# rx20.net
KiCad netlist of a schematic drawn in EAGLE
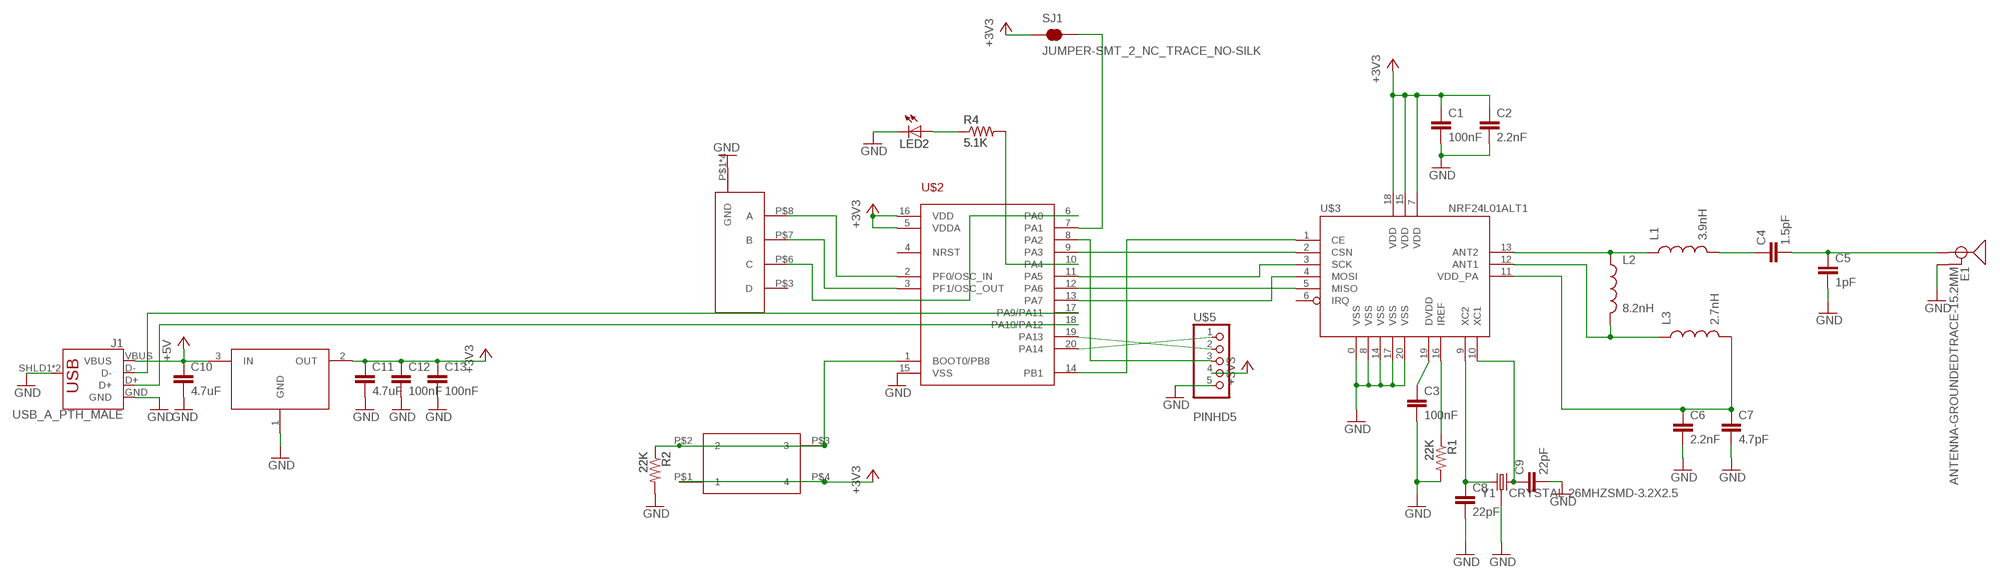
[diagram p0: schematic, sheet 1]

(export (version "E")
  (design (tool "Eeschema 10.0.6"))
  (components
    (comp (ref "C1")
      (value "100nF")
      (footprint "eagle-import:0805")
      (libsource (lib "eagle-import") (part "CAP0805"))
    )
    (comp (ref "C2")
      (value "2.2nF")
      (footprint "eagle-import:0805")
      (libsource (lib "eagle-import") (part "CAP0805"))
    )
    (comp (ref "C3")
      (value "100nF")
      (footprint "eagle-import:0805")
      (libsource (lib "eagle-import") (part "CAP0805"))
    )
    (comp (ref "C4")
      (value "1.5pF")
      (footprint "eagle-import:0805")
      (libsource (lib "eagle-import") (part "CAP0805"))
    )
    (comp (ref "C5")
      (value "1pF")
      (footprint "eagle-import:0805")
      (libsource (lib "eagle-import") (part "CAP0805"))
    )
    (comp (ref "C6")
      (value "2.2nF")
      (footprint "eagle-import:0805")
      (libsource (lib "eagle-import") (part "CAP0805"))
    )
    (comp (ref "C7")
      (value "4.7pF")
      (footprint "eagle-import:0805")
      (libsource (lib "eagle-import") (part "CAP0805"))
    )
    (comp (ref "C8")
      (value "22pF")
      (footprint "eagle-import:0805")
      (libsource (lib "eagle-import") (part "CAP0805"))
    )
    (comp (ref "C9")
      (value "22pF")
      (footprint "eagle-import:0805")
      (libsource (lib "eagle-import") (part "CAP0805"))
    )
    (comp (ref "C10")
      (value "4.7uF")
      (footprint "eagle-import:0805")
      (libsource (lib "eagle-import") (part "CAP0805"))
    )
    (comp (ref "C11")
      (value "4.7uF")
      (footprint "eagle-import:0805")
      (libsource (lib "eagle-import") (part "CAP0805"))
    )
    (comp (ref "C12")
      (value "100nF")
      (footprint "eagle-import:0805")
      (libsource (lib "eagle-import") (part "CAP0805"))
    )
    (comp (ref "C13")
      (value "100nF")
      (footprint "eagle-import:0805")
      (libsource (lib "eagle-import") (part "CAP0805"))
    )
    (comp (ref "E1")
      (value "ANTENNA-GROUNDEDTRACE-15.2MM")
      (footprint "eagle-import:TRACE_ANTENNA_2.4GHZ_15.2MM")
      (libsource (lib "eagle-import") (part "ANTENNA-GROUNDEDTRACE-15.2MM"))
    )
    (comp (ref "J1")
      (value "USB_A_PTH_MALE")
      (footprint "eagle-import:USB-A-H")
      (libsource (lib "eagle-import") (part "USB_A_PTH_MALE"))
    )
    (comp (ref "L1")
      (value "3.9nH")
      (footprint "eagle-import:0805")
      (libsource (lib "eagle-import") (part "INDUCTOR0805"))
    )
    (comp (ref "L2")
      (value "8.2nH")
      (footprint "eagle-import:0805")
      (libsource (lib "eagle-import") (part "INDUCTOR0805"))
    )
    (comp (ref "L3")
      (value "2.7nH")
      (footprint "eagle-import:0805")
      (libsource (lib "eagle-import") (part "INDUCTOR0805"))
    )
    (comp (ref "LED2")
      (value "LEDCHIP-LED0805")
      (footprint "eagle-import:CHIP-LED0805")
      (libsource (lib "eagle-import") (part "LEDCHIP-LED0805"))
    )
    (comp (ref "R1")
      (value "22K")
      (footprint "eagle-import:0805")
      (libsource (lib "eagle-import") (part "RESISTOR0805-RES"))
    )
    (comp (ref "R2")
      (value "22K")
      (footprint "eagle-import:0805")
      (libsource (lib "eagle-import") (part "RESISTOR0805-RES"))
    )
    (comp (ref "R4")
      (value "5.1K")
      (footprint "eagle-import:0805")
      (libsource (lib "eagle-import") (part "RESISTOR0805-RES"))
    )
    (comp (ref "SJ1")
      (value "JUMPER-SMT_2_NC_TRACE_NO-SILK")
      (footprint "eagle-import:SMT-JUMPER_2_NC_TRACE_NO-SILK")
      (libsource (lib "eagle-import") (part "JUMPER-SMT_2_NC_TRACE_NO-SILK"))
    )
    (comp (ref "U$1")
      (value "SW_3POS_DEVSW_3POS_OFFICIAL")
      (footprint "eagle-import:SW_3POS_FOOT_OFFICIAL")
      (libsource (lib "eagle-import") (part "SW_3POS_DEVSW_3POS_OFFICIAL"))
    )
    (comp (ref "U$2")
      (value "STM32F042F4")
      (footprint "eagle-import:TSSOP20")
      (libsource (lib "eagle-import") (part "STM32F042F4"))
    )
    (comp (ref "U$3")
      (value "NRF24L01ALT1")
      (footprint "eagle-import:QFN20_ALT1")
      (libsource (lib "eagle-import") (part "NRF24L01ALT1"))
    )
    (comp (ref "U$4")
      (value "XC6206_DEV")
      (footprint "eagle-import:SOT23R_INFINEON")
      (libsource (lib "eagle-import") (part "XC6206_DEV"))
    )
    (comp (ref "U$5")
      (value "PINHD5")
      (footprint "eagle-import:1X05")
      (libsource (lib "eagle-import") (part "PINHD5"))
    )
    (comp (ref "U$10")
      (value "324_SW")
      (footprint "eagle-import:342_SWICH_FOOT")
      (libsource (lib "eagle-import") (part "324_SW"))
    )
    (comp (ref "Y1")
      (value "CRYSTAL-26MHZSMD-3.2X2.5")
      (footprint "eagle-import:CRYSTAL-SMD-3.2X2.5MM")
      (libsource (lib "eagle-import") (part "CRYSTAL-26MHZSMD-3.2X2.5"))
    )
  )
  (nets
    (net (code "1") (name "+3V3") (class "Default")
      (node (ref "C1") (pin "1") (pinfunction "1_1") (pintype "passive"))
      (node (ref "C11") (pin "1") (pinfunction "1_1") (pintype "passive"))
      (node (ref "C12") (pin "1") (pinfunction "1_1") (pintype "passive"))
      (node (ref "C13") (pin "1") (pinfunction "1_1") (pintype "passive"))
      (node (ref "C2") (pin "1") (pinfunction "1_1") (pintype "passive"))
      (node (ref "SJ1") (pin "1") (pinfunction "1_1") (pintype "passive"))
      (node (ref "U$10") (pin "P$1") (pinfunction "1_P$1") (pintype "bidirectional"))
      (node (ref "U$10") (pin "P$4") (pinfunction "4_P$4") (pintype "bidirectional"))
      (node (ref "U$2") (pin "16") (pinfunction "VDD_16") (pintype "bidirectional"))
      (node (ref "U$2") (pin "5") (pinfunction "VDDA_5") (pintype "bidirectional"))
      (node (ref "U$3") (pin "15") (pinfunction "VDD_15") (pintype "power_in"))
      (node (ref "U$3") (pin "18") (pinfunction "VDD_18") (pintype "power_in"))
      (node (ref "U$3") (pin "7") (pinfunction "VDD_7") (pintype "power_in"))
      (node (ref "U$4") (pin "2") (pinfunction "OUT_2") (pintype "bidirectional"))
      (node (ref "U$5") (pin "4") (pinfunction "4_4") (pintype "passive"))
    )
    (net (code "2") (name "+5V") (class "Default")
      (node (ref "C10") (pin "1") (pinfunction "1_1") (pintype "passive"))
      (node (ref "J1") (pin "VBUS") (pinfunction "VBUS_VBUS") (pintype "power_in"))
      (node (ref "U$4") (pin "3") (pinfunction "IN_3") (pintype "bidirectional"))
    )
    (net (code "3") (name "GND") (class "Default")
      (node (ref "C1") (pin "2") (pinfunction "2_2") (pintype "passive"))
      (node (ref "C10") (pin "2") (pinfunction "2_2") (pintype "passive"))
      (node (ref "C11") (pin "2") (pinfunction "2_2") (pintype "passive"))
      (node (ref "C12") (pin "2") (pinfunction "2_2") (pintype "passive"))
      (node (ref "C13") (pin "2") (pinfunction "2_2") (pintype "passive"))
      (node (ref "C2") (pin "2") (pinfunction "2_2") (pintype "passive"))
      (node (ref "C3") (pin "2") (pinfunction "2_2") (pintype "passive"))
      (node (ref "C5") (pin "2") (pinfunction "2_2") (pintype "passive"))
      (node (ref "C6") (pin "2") (pinfunction "2_2") (pintype "passive"))
      (node (ref "C7") (pin "2") (pinfunction "2_2") (pintype "passive"))
      (node (ref "C8") (pin "2") (pinfunction "2_2") (pintype "passive"))
      (node (ref "C9") (pin "2") (pinfunction "2_2") (pintype "passive"))
      (node (ref "E1") (pin "GND") (pinfunction "GND_GND") (pintype "bidirectional"))
      (node (ref "J1") (pin "GND") (pinfunction "GND_GND") (pintype "power_in"))
      (node (ref "J1") (pin "SHLD1") (pinfunction "SHIELD_SHLD1") (pintype "bidirectional"))
      (node (ref "J1") (pin "SHLD2") (pinfunction "SHIELD_SHLD2") (pintype "bidirectional"))
      (node (ref "LED2") (pin "C") (pinfunction "C_C") (pintype "passive"))
      (node (ref "R1") (pin "2") (pinfunction "2_2") (pintype "passive"))
      (node (ref "R2") (pin "2") (pinfunction "2_2") (pintype "passive"))
      (node (ref "U$1") (pin "P$1") (pinfunction "GND_P$1") (pintype "bidirectional"))
      (node (ref "U$1") (pin "P$2") (pinfunction "GND_P$2") (pintype "bidirectional"))
      (node (ref "U$1") (pin "P$4") (pinfunction "GND_P$4") (pintype "bidirectional"))
      (node (ref "U$1") (pin "P$5") (pinfunction "GND_P$5") (pintype "bidirectional"))
      (node (ref "U$2") (pin "15") (pinfunction "VSS_15") (pintype "bidirectional"))
      (node (ref "U$3") (pin "0") (pinfunction "VSS_0") (pintype "power_in"))
      (node (ref "U$3") (pin "14") (pinfunction "VSS_14") (pintype "power_in"))
      (node (ref "U$3") (pin "17") (pinfunction "VSS_17") (pintype "power_in"))
      (node (ref "U$3") (pin "20") (pinfunction "VSS_20") (pintype "power_in"))
      (node (ref "U$3") (pin "8") (pinfunction "VSS_8") (pintype "power_in"))
      (node (ref "U$4") (pin "1") (pinfunction "GND_1") (pintype "bidirectional"))
      (node (ref "U$5") (pin "5") (pinfunction "5_5") (pintype "passive"))
      (node (ref "Y1") (pin "2") (pinfunction "3_2") (pintype "passive"))
      (node (ref "Y1") (pin "4") (pinfunction "3_4") (pintype "passive"))
    )
    (net (code "4") (name "Net-(C4-Pad1)") (class "Default")
      (node (ref "C4") (pin "1") (pinfunction "1_1") (pintype "passive"))
      (node (ref "L1") (pin "2") (pinfunction "2_2") (pintype "passive"))
    )
    (net (code "5") (name "Net-(E1-SIGNAL)") (class "Default")
      (node (ref "C4") (pin "2") (pinfunction "2_2") (pintype "passive"))
      (node (ref "C5") (pin "1") (pinfunction "1_1") (pintype "passive"))
      (node (ref "E1") (pin "ANT") (pinfunction "SIGNAL_ANT") (pintype "bidirectional"))
    )
    (net (code "6") (name "Net-(LED2-PadA)") (class "Default")
      (node (ref "LED2") (pin "A") (pinfunction "A_A") (pintype "passive"))
      (node (ref "R4") (pin "1") (pinfunction "1_1") (pintype "passive"))
    )
    (net (code "7") (name "Net-(U$1-A)") (class "Default")
      (node (ref "U$1") (pin "P$8") (pinfunction "A_P$8") (pintype "bidirectional"))
      (node (ref "U$2") (pin "2") (pinfunction "PF0/OSC_IN_2") (pintype "bidirectional"))
    )
    (net (code "8") (name "Net-(U$1-B)") (class "Default")
      (node (ref "U$1") (pin "P$7") (pinfunction "B_P$7") (pintype "bidirectional"))
      (node (ref "U$2") (pin "3") (pinfunction "PF1/OSC_OUT_3") (pintype "bidirectional"))
    )
    (net (code "9") (name "Net-(U$1-C)") (class "Default")
      (node (ref "U$1") (pin "P$6") (pinfunction "C_P$6") (pintype "bidirectional"))
      (node (ref "U$2") (pin "6") (pinfunction "PA0_6") (pintype "bidirectional"))
    )
    (net (code "10") (name "Net-(U$2-PA1)") (class "Default")
      (node (ref "SJ1") (pin "2") (pinfunction "2_2") (pintype "passive"))
      (node (ref "U$2") (pin "7") (pinfunction "PA1_7") (pintype "bidirectional"))
    )
    (net (code "11") (name "Net-(U$2-PA2)") (class "Default")
      (node (ref "U$2") (pin "8") (pinfunction "PA2_8") (pintype "bidirectional"))
      (node (ref "U$5") (pin "3") (pinfunction "3_3") (pintype "passive"))
    )
    (net (code "12") (name "Net-(U$2-PA3)") (class "Default")
      (node (ref "U$2") (pin "9") (pinfunction "PA3_9") (pintype "bidirectional"))
      (node (ref "U$3") (pin "2") (pinfunction "CSN_2") (pintype "input"))
    )
    (net (code "13") (name "Net-(U$2-PA4)") (class "Default")
      (node (ref "R4") (pin "2") (pinfunction "2_2") (pintype "passive"))
      (node (ref "U$2") (pin "10") (pinfunction "PA4_10") (pintype "bidirectional"))
    )
    (net (code "14") (name "Net-(U$2-PA5)") (class "Default")
      (node (ref "U$2") (pin "11") (pinfunction "PA5_11") (pintype "bidirectional"))
      (node (ref "U$3") (pin "3") (pinfunction "SCK_3") (pintype "input"))
    )
    (net (code "15") (name "Net-(U$2-PA6)") (class "Default")
      (node (ref "U$2") (pin "12") (pinfunction "PA6_12") (pintype "bidirectional"))
      (node (ref "U$3") (pin "5") (pinfunction "MISO_5") (pintype "output"))
    )
    (net (code "16") (name "Net-(U$2-PA7)") (class "Default")
      (node (ref "U$2") (pin "13") (pinfunction "PA7_13") (pintype "bidirectional"))
      (node (ref "U$3") (pin "4") (pinfunction "MOSI_4") (pintype "input"))
    )
    (net (code "17") (name "Net-(U$2-PA9{slash}PA11)") (class "Default")
      (node (ref "J1") (pin "D-") (pinfunction "D-_D-") (pintype "bidirectional"))
      (node (ref "U$2") (pin "17") (pinfunction "PA9/PA11_17") (pintype "bidirectional"))
    )
    (net (code "18") (name "Net-(U$2-PA10{slash}PA12)") (class "Default")
      (node (ref "J1") (pin "D+") (pinfunction "D+_D+") (pintype "bidirectional"))
      (node (ref "U$2") (pin "18") (pinfunction "PA10/PA12_18") (pintype "bidirectional"))
    )
    (net (code "19") (name "Net-(U$2-PA13)") (class "Default")
      (node (ref "U$2") (pin "19") (pinfunction "PA13_19") (pintype "bidirectional"))
      (node (ref "U$5") (pin "2") (pinfunction "2_2") (pintype "passive"))
    )
    (net (code "20") (name "Net-(U$2-PA14)") (class "Default")
      (node (ref "U$2") (pin "20") (pinfunction "PA14_20") (pintype "bidirectional"))
      (node (ref "U$5") (pin "1") (pinfunction "1_1") (pintype "passive"))
    )
    (net (code "21") (name "Net-(U$2-PB1)") (class "Default")
      (node (ref "U$2") (pin "14") (pinfunction "PB1_14") (pintype "bidirectional"))
      (node (ref "U$3") (pin "1") (pinfunction "CE_1") (pintype "input"))
    )
    (net (code "22") (name "Net-(U$3-ANT1)") (class "Default")
      (node (ref "L2") (pin "2") (pinfunction "2_2") (pintype "passive"))
      (node (ref "L3") (pin "1") (pinfunction "1_1") (pintype "passive"))
      (node (ref "U$3") (pin "12") (pinfunction "ANT1_12") (pintype "output"))
    )
    (net (code "23") (name "Net-(U$3-ANT2)") (class "Default")
      (node (ref "L1") (pin "1") (pinfunction "1_1") (pintype "passive"))
      (node (ref "L2") (pin "1") (pinfunction "1_1") (pintype "passive"))
      (node (ref "U$3") (pin "13") (pinfunction "ANT2_13") (pintype "output"))
    )
    (net (code "24") (name "Net-(U$3-DVDD)") (class "Default")
      (node (ref "C3") (pin "1") (pinfunction "1_1") (pintype "passive"))
      (node (ref "U$3") (pin "19") (pinfunction "DVDD_19") (pintype "power_in"))
    )
    (net (code "25") (name "Net-(U$3-IREF)") (class "Default")
      (node (ref "R1") (pin "1") (pinfunction "1_1") (pintype "passive"))
      (node (ref "U$3") (pin "16") (pinfunction "IREF_16") (pintype "input"))
    )
    (net (code "26") (name "Net-(U$3-VDD_PA)") (class "Default")
      (node (ref "C6") (pin "1") (pinfunction "1_1") (pintype "passive"))
      (node (ref "C7") (pin "1") (pinfunction "1_1") (pintype "passive"))
      (node (ref "L3") (pin "2") (pinfunction "2_2") (pintype "passive"))
      (node (ref "U$3") (pin "11") (pinfunction "VDD_PA_11") (pintype "power_in"))
    )
    (net (code "27") (name "Net-(U$3-XC1)") (class "Default")
      (node (ref "C9") (pin "1") (pinfunction "1_1") (pintype "passive"))
      (node (ref "U$3") (pin "10") (pinfunction "XC1_10") (pintype "input"))
      (node (ref "Y1") (pin "3") (pinfunction "2_3") (pintype "passive"))
    )
    (net (code "28") (name "Net-(U$3-XC2)") (class "Default")
      (node (ref "C8") (pin "1") (pinfunction "1_1") (pintype "passive"))
      (node (ref "U$3") (pin "9") (pinfunction "XC2_9") (pintype "input"))
      (node (ref "Y1") (pin "1") (pinfunction "1_1") (pintype "passive"))
    )
    (net (code "29") (name "Net-(U$10-2)") (class "Default")
      (node (ref "R2") (pin "1") (pinfunction "1_1") (pintype "passive"))
      (node (ref "U$10") (pin "P$2") (pinfunction "2_P$2") (pintype "bidirectional"))
      (node (ref "U$10") (pin "P$3") (pinfunction "3_P$3") (pintype "bidirectional"))
      (node (ref "U$2") (pin "1") (pinfunction "BOOT0/PB8_1") (pintype "bidirectional"))
    )
    (net (code "30") (name "unconnected-(U$1-D-PadP$3)") (class "Default")
      (node (ref "U$1") (pin "P$3") (pinfunction "D_P$3") (pintype "bidirectional"))
    )
    (net (code "31") (name "unconnected-(U$2-NRST-Pad4)") (class "Default")
      (node (ref "U$2") (pin "4") (pinfunction "NRST_4") (pintype "bidirectional"))
    )
    (net (code "32") (name "unconnected-(U$3-IRQ-Pad6)") (class "Default")
      (node (ref "U$3") (pin "6") (pinfunction "IRQ_6") (pintype "output"))
    )
  )
)
